# A1-A1_Gain_control_driver.net
KiCad netlist of a schematic drawn in Altium Designer
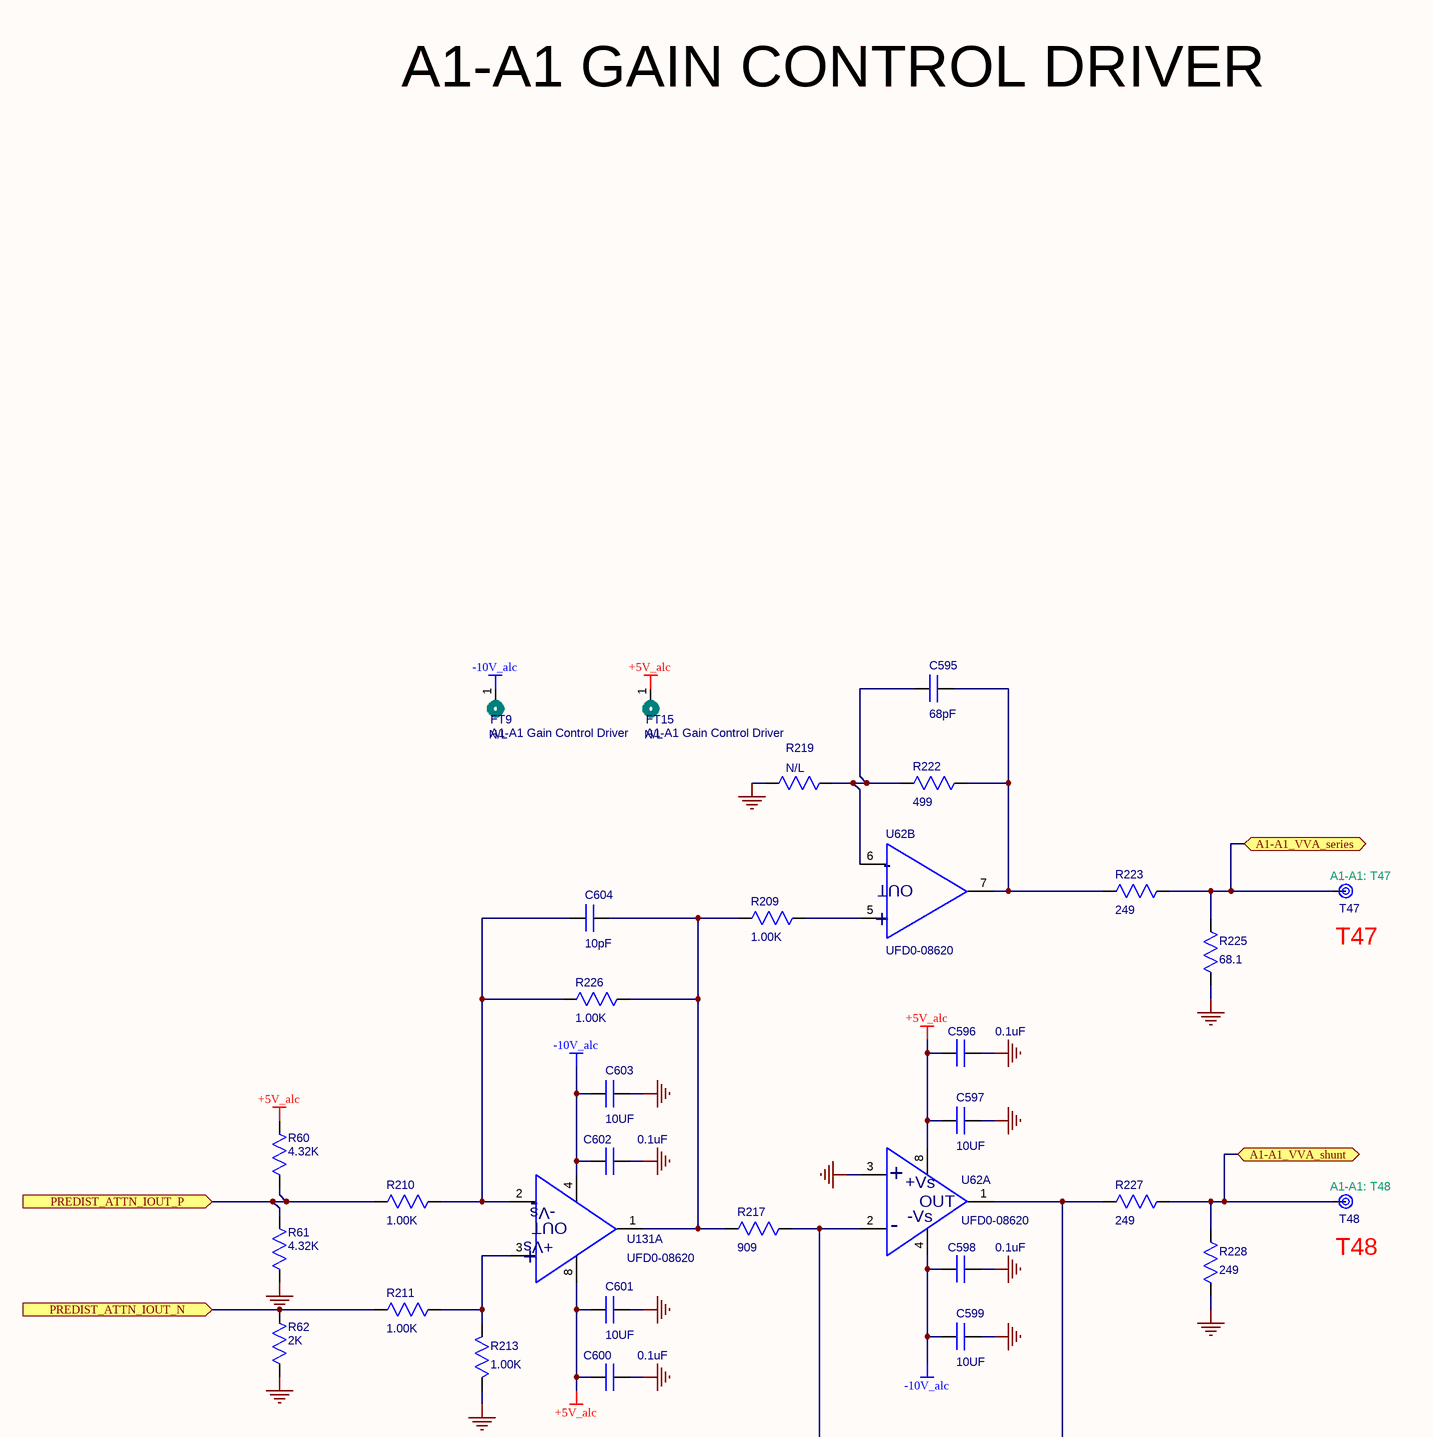
[diagram p0: A1-A1 Gain control driver.SchDoc, top right]
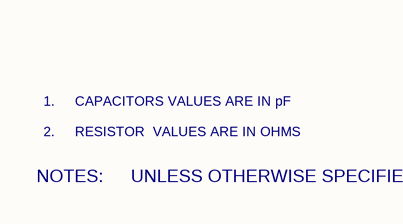
[diagram p1: A1-A1 Gain control driver.SchDoc, bottom left]
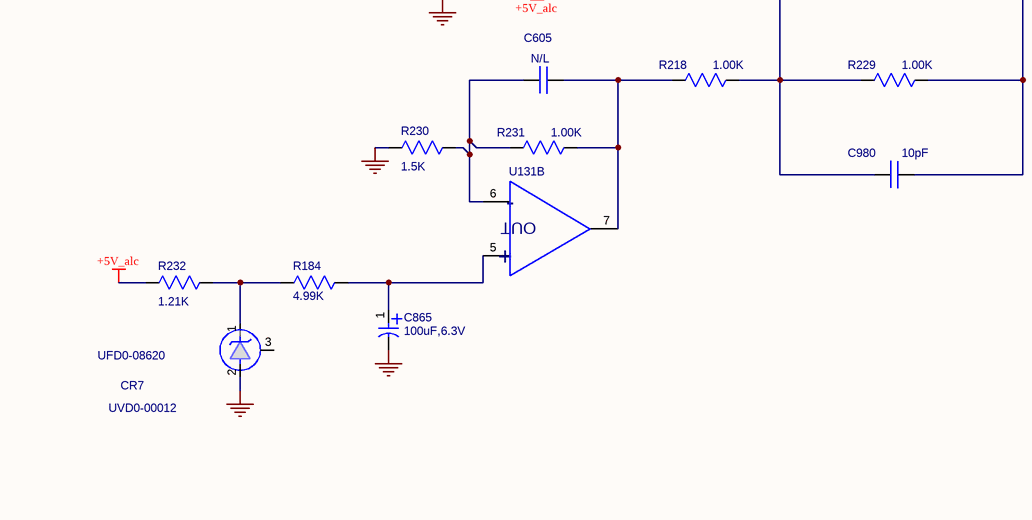
[diagram p2: A1-A1 Gain control driver.SchDoc, bottom right]

(export (version "E")
  (design (tool "Eeschema 10.0.6"))
  (components
    (comp (ref "C595")
      (value "68pF")
      (footprint "CAP-0402-N")
      (description "68pF;5%;COG;50V;CHIP;0402")
      (fields (field (name "APPROVED") "CL"))
      (libsource (lib "Giga-tronics") (part "CK40-00680"))
    )
    (comp (ref "C596")
      (value "0.1uF")
      (footprint "CAP-0603-H035-N")
      (description ".1UF;10%;X7R;16V;CHIP;0603")
      (fields (field (name "APPROVED") "CL"))
      (libsource (lib "Giga-tronics") (part "CK45-04100"))
    )
    (comp (ref "C597")
      (value "10UF")
      (footprint "CAP-1210-N")
      (description "10uF 10% X7R CERAMIC 16V 1210 CHIP")
      (fields (field (name "APPROVED") "XiaoXiao"))
      (libsource (lib "Giga-tronics") (part "CK60-06100"))
    )
    (comp (ref "C598")
      (value "0.1uF")
      (footprint "CAP-0603-H035-N")
      (description ".1UF;10%;X7R;16V;CHIP;0603")
      (fields (field (name "APPROVED") "CL"))
      (libsource (lib "Giga-tronics") (part "CK45-04100"))
    )
    (comp (ref "C599")
      (value "10UF")
      (footprint "CAP-1210-N")
      (description "10uF 10% X7R CERAMIC 16V 1210 CHIP")
      (fields (field (name "APPROVED") "XiaoXiao"))
      (libsource (lib "Giga-tronics") (part "CK60-06100"))
    )
    (comp (ref "C600")
      (value "0.1uF")
      (footprint "CAP-0603-H035-N")
      (description ".1UF;10%;X7R;16V;CHIP;0603")
      (fields (field (name "APPROVED") "CL"))
      (libsource (lib "Giga-tronics") (part "CK45-04100"))
    )
    (comp (ref "C601")
      (value "10UF")
      (footprint "CAP-1210-N")
      (description "10uF 10% X7R CERAMIC 16V 1210 CHIP")
      (fields (field (name "APPROVED") "XiaoXiao"))
      (libsource (lib "Giga-tronics") (part "CK60-06100"))
    )
    (comp (ref "C602")
      (value "0.1uF")
      (footprint "CAP-0603-H035-N")
      (description ".1UF;10%;X7R;16V;CHIP;0603")
      (fields (field (name "APPROVED") "CL"))
      (libsource (lib "Giga-tronics") (part "CK45-04100"))
    )
    (comp (ref "C603")
      (value "10UF")
      (footprint "CAP-1210-N")
      (description "10uF 10% X7R CERAMIC 16V 1210 CHIP")
      (fields (field (name "APPROVED") "XiaoXiao"))
      (libsource (lib "Giga-tronics") (part "CK60-06100"))
    )
    (comp (ref "C604")
      (value "10pF")
      (footprint "CAP-0402-N")
      (description "10 PF;5%;COG;>50V;CHIP;0402")
      (fields (field (name "APPROVED") "CL"))
      (libsource (lib "Giga-tronics") (part "CK40-00100"))
    )
    (comp (ref "C605")
      (value "2.2pF;5%;COG;50V;CHIP;0402")
      (footprint "CAP-0402-N")
      (fields (field (name "NOLOAD") "N/L") (field (name "APPROVED") "CL"))
      (libsource (lib "Giga-tronics") (part "CK40-00022"))
    )
    (comp (ref "C865")
      (value "100uF,6.3V")
      (footprint "CAPP-3528-21-N")
      (description "100UF;20%;6.3V;.04 ESR;POLY TANT;3528")
      (fields (field (name "APPROVED") "CL"))
      (libsource (lib "Giga-tronics") (part "CT06-S7100"))
    )
    (comp (ref "C980")
      (value "10pF")
      (footprint "CAP-0402-N")
      (description "10 PF;5%;COG;>50V;CHIP;0402")
      (fields (field (name "APPROVED") "CL"))
      (libsource (lib "Giga-tronics") (part "CK40-00100"))
    )
    (comp (ref "CR7")
      (value "VREF;1.235V;+/-4MV;.2MV 0-70 DEG C;SOT-23")
      (footprint "SOT23-N")
      (fields (field (name "G_PN") "UVD0-00012") (field (name "APPROVED") "CL"))
      (libsource (lib "Giga-tronics") (part "UVD0-00012"))
    )
    (comp (ref "FT9")
      (value "A1-A1 Gain Control Driver")
      (footprint "FromToNode_ML2")
      (fields (field (name "NOLOAD") "N/L") (field (name "APPROVED") "*"))
      (libsource (lib "Giga-tronics") (part "FromToNode"))
    )
    (comp (ref "FT15")
      (value "A1-A1 Gain Control Driver")
      (footprint "FromToNode_ML2")
      (fields (field (name "NOLOAD") "N/L") (field (name "APPROVED") "*"))
      (libsource (lib "Giga-tronics") (part "FromToNode"))
    )
    (comp (ref "R60")
      (value "4.32K")
      (footprint "RES-0201-N")
      (description "4.32 OHMS;.05W;1%;100PPM;FILM CHIP;0201")
      (fields (field (name "APPROVED") "CL"))
      (libsource (lib "Giga-tronics") (part "RK30-14320"))
    )
    (comp (ref "R61")
      (value "4.32K")
      (footprint "RES-0201-N")
      (description "4.32 OHMS;.05W;1%;100PPM;FILM CHIP;0201")
      (fields (field (name "APPROVED") "CL"))
      (libsource (lib "Giga-tronics") (part "RK30-14320"))
    )
    (comp (ref "R62")
      (value "2K")
      (footprint "RES-0201-N")
      (description "2 KOHMS;.05W;1%;100PPM;FILM CHIP;0201")
      (fields (field (name "APPROVED") "CL"))
      (libsource (lib "Giga-tronics") (part "RK30-12000"))
    )
    (comp (ref "R184")
      (value "4.99K")
      (footprint "RES-0402-N")
      (description "4.99K OHMS;.06W;1%;200PPM;FILM;CHIP;0402")
      (fields (field (name "APPROVED") "CL"))
      (libsource (lib "Giga-tronics") (part "RK35-14990"))
    )
    (comp (ref "R209")
      (value "1.00K")
      (footprint "RES-0402-N")
      (description "1.0K OHMS;.06W;1%;200PPM;FILM;CHIP;0402")
      (fields (field (name "APPROVED") "CL"))
      (libsource (lib "Giga-tronics") (part "RK35-11000"))
    )
    (comp (ref "R210")
      (value "1.00K")
      (footprint "RES-0402-N")
      (description "1.0K OHMS;.06W;1%;200PPM;FILM;CHIP;0402")
      (fields (field (name "APPROVED") "CL"))
      (libsource (lib "Giga-tronics") (part "RK35-11000"))
    )
    (comp (ref "R211")
      (value "1.00K")
      (footprint "RES-0402-N")
      (description "1.0K OHMS;.06W;1%;200PPM;FILM;CHIP;0402")
      (fields (field (name "APPROVED") "CL"))
      (libsource (lib "Giga-tronics") (part "RK35-11000"))
    )
    (comp (ref "R213")
      (value "1.00K")
      (footprint "RES-0402-N")
      (description "1.0K OHMS;.06W;1%;200PPM;FILM;CHIP;0402")
      (fields (field (name "APPROVED") "CL"))
      (libsource (lib "Giga-tronics") (part "RK35-11000"))
    )
    (comp (ref "R217")
      (value "909")
      (footprint "RES-0402-N")
      (description "909 OHMS; 1%; .1W; 100PPM; FILM; CHIP; 0402")
      (fields (field (name "APPROVED") "CL"))
      (libsource (lib "Giga-tronics") (part "RK35-09090"))
    )
    (comp (ref "R218")
      (value "1.00K")
      (footprint "RES-0402-N")
      (description "1.0K OHMS;.06W;1%;200PPM;FILM;CHIP;0402")
      (fields (field (name "APPROVED") "CL"))
      (libsource (lib "Giga-tronics") (part "RK35-11000"))
    )
    (comp (ref "R219")
      (value "32.4K OHMS;.06W;1%;200PPM;FILM;CHIP;0402")
      (footprint "RES-0402-N")
      (fields (field (name "NOLOAD") "N/L") (field (name "APPROVED") "CL"))
      (libsource (lib "Giga-tronics") (part "RK35-23240"))
    )
    (comp (ref "R222")
      (value "499")
      (footprint "RES-0402-N")
      (description "499 OHMS; 1%; .1W; 100PPM; FILM; CHIP; 0402")
      (fields (field (name "APPROVED") "CL"))
      (libsource (lib "Giga-tronics") (part "RK35-04990"))
    )
    (comp (ref "R223")
      (value "249")
      (footprint "RES-0402-N")
      (description "249 OHMS; 1%; .1W; 100PPM; FILM; CHIP; 0402")
      (fields (field (name "APPROVED") "CL"))
      (libsource (lib "Giga-tronics") (part "RK35-02490"))
    )
    (comp (ref "R225")
      (value "68.1")
      (footprint "RES-0402-N")
      (description "68.1 OHMS;.06W;1%;200PPM;FILM;CHIP;0402")
      (fields (field (name "APPROVED") "CL"))
      (libsource (lib "Giga-tronics") (part "RK35-00681"))
    )
    (comp (ref "R226")
      (value "1.00K")
      (footprint "RES-0402-N")
      (description "1.0K OHMS;.06W;1%;200PPM;FILM;CHIP;0402")
      (fields (field (name "APPROVED") "CL"))
      (libsource (lib "Giga-tronics") (part "RK35-11000"))
    )
    (comp (ref "R227")
      (value "249")
      (footprint "RES-0402-N")
      (description "249 OHMS; 1%; .1W; 100PPM; FILM; CHIP; 0402")
      (fields (field (name "APPROVED") "CL"))
      (libsource (lib "Giga-tronics") (part "RK35-02490"))
    )
    (comp (ref "R228")
      (value "249")
      (footprint "RES-0402-N")
      (description "249 OHMS; 1%; .1W; 100PPM; FILM; CHIP; 0402")
      (fields (field (name "APPROVED") "CL"))
      (libsource (lib "Giga-tronics") (part "RK35-02490"))
    )
    (comp (ref "R229")
      (value "1.00K")
      (footprint "RES-0402-N")
      (description "1.0K OHMS;.06W;1%;200PPM;FILM;CHIP;0402")
      (fields (field (name "APPROVED") "CL"))
      (libsource (lib "Giga-tronics") (part "RK35-11000"))
    )
    (comp (ref "R230")
      (value "1.5K")
      (footprint "RES-0402-N")
      (description "1.50K Ohms;.06W;1%;±100PPM;CHIP RES;0402")
      (fields (field (name "APPROVED") "CL"))
      (libsource (lib "Giga-tronics") (part "RK35-11500"))
    )
    (comp (ref "R231")
      (value "1.00K")
      (footprint "RES-0402-N")
      (description "1.0K OHMS;.06W;1%;200PPM;FILM;CHIP;0402")
      (fields (field (name "APPROVED") "CL"))
      (libsource (lib "Giga-tronics") (part "RK35-11000"))
    )
    (comp (ref "R232")
      (value "1.21K")
      (footprint "RES-0402-N")
      (description "1.21K OHMS;.06W;1%;200PPM;FILM;CHIP;0402")
      (fields (field (name "APPROVED") "CL"))
      (libsource (lib "Giga-tronics") (part "RK35-11210"))
    )
    (comp (ref "T47")
      (value "A1-A1: T47")
      (footprint "JIB0-11254")
      (description "SOCKET;SINGLE;.018-.040 ID X .254;OPEN;GLD")
      (fields (field (name "APPROVED") "NM"))
      (libsource (lib "Giga-tronics") (part "JIB0-11254"))
    )
    (comp (ref "T48")
      (value "A1-A1: T48")
      (footprint "JIB0-11254")
      (description "SOCKET;SINGLE;.018-.040 ID X .254;OPEN;GLD")
      (fields (field (name "APPROVED") "NM"))
      (libsource (lib "Giga-tronics") (part "JIB0-11254"))
    )
    (comp (ref "U62")
      (value "OP-AMP;DUAL:PRECISION;LOW CURRENT;LOW NOISE;WIDE")
      (footprint "SO8_MS-012")
      (fields (field (name "G_PN") "UFD0-08620") (field (name "APPROVED") "CL"))
      (libsource (lib "Giga-tronics") (part "UFD0-08620"))
    )
    (comp (ref "U131")
      (value "OP-AMP;DUAL:PRECISION;LOW CURRENT;LOW NOISE;WIDE")
      (footprint "SO8_MS-012")
      (fields (field (name "G_PN") "UFD0-08620") (field (name "APPROVED") "CL"))
      (libsource (lib "Giga-tronics") (part "UFD0-08620"))
    )
  )
  (nets
    (net (code "1") (name "+5V_alc") (class "Default")
      (node (ref "C596") (pin "1") (pintype "passive"))
      (node (ref "C597") (pin "1") (pintype "passive"))
      (node (ref "C600") (pin "1") (pintype "passive"))
      (node (ref "C601") (pin "1") (pintype "passive"))
      (node (ref "FT15") (pin "1") (pinfunction "1_1") (pintype "passive"))
      (node (ref "R232") (pin "1") (pintype "passive"))
      (node (ref "R60") (pin "2") (pintype "passive"))
      (node (ref "U131") (pin "8") (pinfunction "V+_8") (pintype "passive"))
      (node (ref "U62") (pin "8") (pinfunction "V+_8") (pintype "passive"))
    )
    (net (code "2") (name "-10V_alc") (class "Default")
      (node (ref "C598") (pin "1") (pintype "passive"))
      (node (ref "C599") (pin "1") (pintype "passive"))
      (node (ref "C602") (pin "1") (pintype "passive"))
      (node (ref "C603") (pin "1") (pintype "passive"))
      (node (ref "FT9") (pin "1") (pinfunction "1_1") (pintype "passive"))
      (node (ref "U131") (pin "4") (pinfunction "V-_4") (pintype "passive"))
      (node (ref "U62") (pin "4") (pinfunction "V-_4") (pintype "passive"))
    )
    (net (code "3") (name "/A1-A1_VVA_series") (class "Default")
      (node (ref "R223") (pin "2") (pintype "passive"))
      (node (ref "R225") (pin "2") (pintype "passive"))
      (node (ref "T47") (pin "1") (pintype "passive"))
    )
    (net (code "4") (name "/A1-A1_VVA_shunt") (class "Default")
      (node (ref "R227") (pin "2") (pintype "passive"))
      (node (ref "R228") (pin "2") (pintype "passive"))
      (node (ref "T48") (pin "1") (pintype "passive"))
    )
    (net (code "5") (name "/PREDIST_ATTN_IOUT_N") (class "Default")
      (node (ref "R211") (pin "1") (pintype "passive"))
      (node (ref "R62") (pin "2") (pintype "passive"))
    )
    (net (code "6") (name "/PREDIST_ATTN_IOUT_P") (class "Default")
      (node (ref "R210") (pin "1") (pintype "passive"))
      (node (ref "R60") (pin "1") (pintype "passive"))
      (node (ref "R61") (pin "2") (pintype "passive"))
    )
    (net (code "7") (name "GND") (class "Default")
      (node (ref "C596") (pin "2") (pintype "passive"))
      (node (ref "C597") (pin "2") (pintype "passive"))
      (node (ref "C598") (pin "2") (pintype "passive"))
      (node (ref "C599") (pin "2") (pintype "passive"))
      (node (ref "C600") (pin "2") (pintype "passive"))
      (node (ref "C601") (pin "2") (pintype "passive"))
      (node (ref "C602") (pin "2") (pintype "passive"))
      (node (ref "C603") (pin "2") (pintype "passive"))
      (node (ref "C865") (pin "2") (pinfunction "NEG_2") (pintype "passive"))
      (node (ref "CR7") (pin "2") (pinfunction "A_2") (pintype "passive"))
      (node (ref "R213") (pin "2") (pintype "passive"))
      (node (ref "R219") (pin "1") (pintype "passive"))
      (node (ref "R225") (pin "1") (pintype "passive"))
      (node (ref "R228") (pin "1") (pintype "passive"))
      (node (ref "R230") (pin "1") (pintype "passive"))
      (node (ref "R61") (pin "1") (pintype "passive"))
      (node (ref "R62") (pin "1") (pintype "passive"))
      (node (ref "U62") (pin "3") (pinfunction "+IN_3") (pintype "passive"))
    )
    (net (code "8") (name "Net-(C865-POS)") (class "Default")
      (node (ref "C865") (pin "1") (pinfunction "POS_1") (pintype "passive"))
      (node (ref "R184") (pin "2") (pintype "passive"))
      (node (ref "U131") (pin "5") (pinfunction "+IN_5") (pintype "passive"))
    )
    (net (code "9") (name "Net-(CR7-C)") (class "Default")
      (node (ref "CR7") (pin "1") (pinfunction "C_1") (pintype "passive"))
      (node (ref "R184") (pin "1") (pintype "passive"))
      (node (ref "R232") (pin "2") (pintype "passive"))
    )
    (net (code "10") (name "Net-(U62A--IN)") (class "Default")
      (node (ref "C980") (pin "1") (pintype "passive"))
      (node (ref "R217") (pin "2") (pintype "passive"))
      (node (ref "R218") (pin "2") (pintype "passive"))
      (node (ref "R229") (pin "1") (pintype "passive"))
      (node (ref "U62") (pin "2") (pinfunction "-IN_2") (pintype "passive"))
    )
    (net (code "11") (name "Net-(U62A-OUT)") (class "Default")
      (node (ref "C980") (pin "2") (pintype "passive"))
      (node (ref "R227") (pin "1") (pintype "passive"))
      (node (ref "R229") (pin "2") (pintype "passive"))
      (node (ref "U62") (pin "1") (pinfunction "OUT_1") (pintype "passive"))
    )
    (net (code "12") (name "Net-(U62B-+IN)") (class "Default")
      (node (ref "R209") (pin "2") (pintype "passive"))
      (node (ref "U62") (pin "5") (pinfunction "+IN_5") (pintype "passive"))
    )
    (net (code "13") (name "Net-(U62B--IN)") (class "Default")
      (node (ref "C595") (pin "1") (pintype "passive"))
      (node (ref "R219") (pin "2") (pintype "passive"))
      (node (ref "R222") (pin "1") (pintype "passive"))
      (node (ref "U62") (pin "6") (pinfunction "-IN_6") (pintype "passive"))
    )
    (net (code "14") (name "Net-(U62B-OUT)") (class "Default")
      (node (ref "C595") (pin "2") (pintype "passive"))
      (node (ref "R222") (pin "2") (pintype "passive"))
      (node (ref "R223") (pin "1") (pintype "passive"))
      (node (ref "U62") (pin "7") (pinfunction "OUT_7") (pintype "passive"))
    )
    (net (code "15") (name "Net-(U131A-+IN)") (class "Default")
      (node (ref "R211") (pin "2") (pintype "passive"))
      (node (ref "R213") (pin "1") (pintype "passive"))
      (node (ref "U131") (pin "3") (pinfunction "+IN_3") (pintype "passive"))
    )
    (net (code "16") (name "Net-(U131A--IN)") (class "Default")
      (node (ref "C604") (pin "1") (pintype "passive"))
      (node (ref "R210") (pin "2") (pintype "passive"))
      (node (ref "R226") (pin "1") (pintype "passive"))
      (node (ref "U131") (pin "2") (pinfunction "-IN_2") (pintype "passive"))
    )
    (net (code "17") (name "Net-(U131A-OUT)") (class "Default")
      (node (ref "C604") (pin "2") (pintype "passive"))
      (node (ref "R209") (pin "1") (pintype "passive"))
      (node (ref "R217") (pin "1") (pintype "passive"))
      (node (ref "R226") (pin "2") (pintype "passive"))
      (node (ref "U131") (pin "1") (pinfunction "OUT_1") (pintype "passive"))
    )
    (net (code "18") (name "Net-(U131B--IN)") (class "Default")
      (node (ref "C605") (pin "1") (pintype "passive"))
      (node (ref "R230") (pin "2") (pintype "passive"))
      (node (ref "R231") (pin "1") (pintype "passive"))
      (node (ref "U131") (pin "6") (pinfunction "-IN_6") (pintype "passive"))
    )
    (net (code "19") (name "Net-(U131B-OUT)") (class "Default")
      (node (ref "C605") (pin "2") (pintype "passive"))
      (node (ref "R218") (pin "1") (pintype "passive"))
      (node (ref "R231") (pin "2") (pintype "passive"))
      (node (ref "U131") (pin "7") (pinfunction "OUT_7") (pintype "passive"))
    )
    (net (code "20") (name "unconnected-(CR7-Pad2)") (class "Default")
      (node (ref "CR7") (pin "2") (pintype "passive"))
    )
    (net (code "21") (name "unconnected-(CR7-case-Pad3)") (class "Default")
      (node (ref "CR7") (pin "3") (pinfunction "case_3") (pintype "passive"))
    )
  )
)
